# FMC_ADC_128CH_10B.net
KiCad netlist of a schematic drawn in Altium Designer
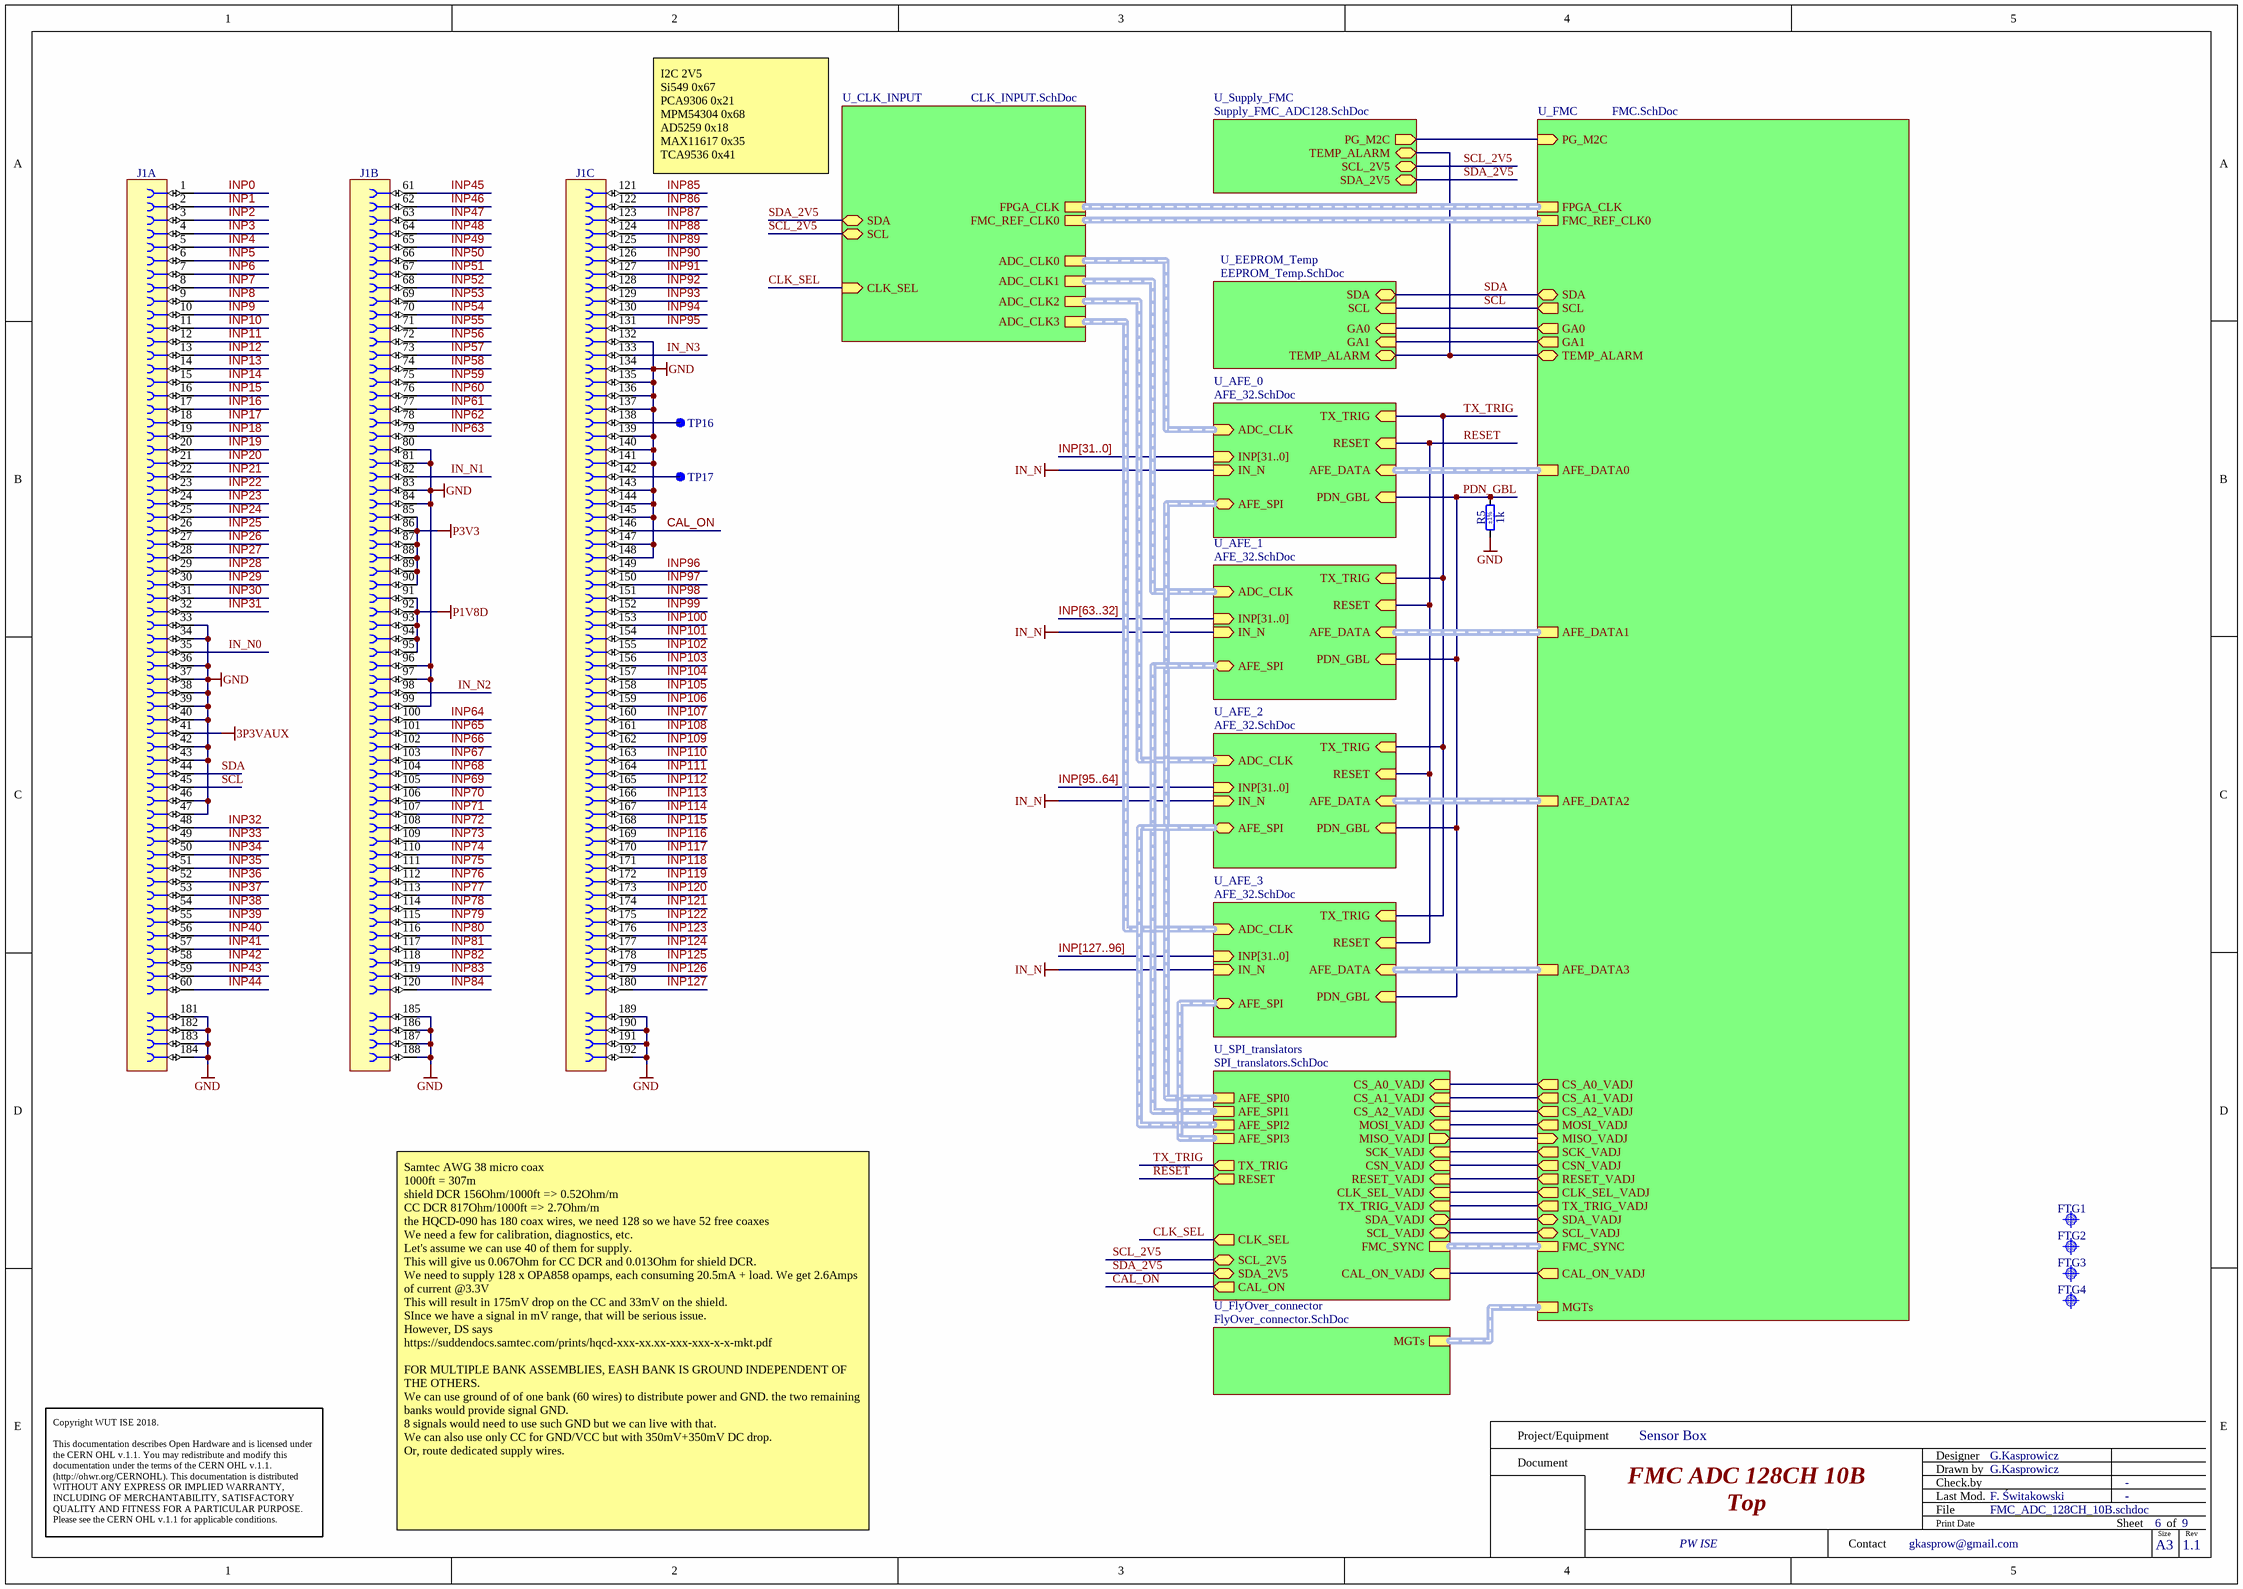
[diagram p0: FMC_ADC_128CH_10B.schdoc]

(export (version "E")
  (design (tool "Eeschema 10.0.6"))
  (components
    (comp (ref "FTG1")
      (value "Use only in PCB")
      (footprint "FIDUCIAL_TOP_C100-200")
      (description "Fiducial Target")
      (fields (field (name "PART NUMBER") "FIDUCIAL_TARGET_C100-200") (field (name "AUTHOR") "CERN DEM JLC"))
      (libsource (lib "Eletro-mechanical") (part "Fiducial Target"))
    )
    (comp (ref "FTG2")
      (value "Use only in PCB")
      (footprint "FIDUCIAL_TOP_S100-200")
      (description "Fiducial Target")
      (fields (field (name "PART NUMBER") "FIDUCIAL_TARGET_S100-200") (field (name "AUTHOR") "CERN DEM JLC"))
      (libsource (lib "Eletro-mechanical") (part "Fiducial Target"))
    )
    (comp (ref "FTG3")
      (value "Use only in PCB")
      (footprint "FIDUCIAL_TOP_C100-200")
      (description "Fiducial Target")
      (fields (field (name "PART NUMBER") "FIDUCIAL_TARGET_C100-200") (field (name "AUTHOR") "CERN DEM JLC"))
      (libsource (lib "Eletro-mechanical") (part "Fiducial Target"))
    )
    (comp (ref "FTG4")
      (value "Use only in PCB")
      (footprint "FIDUCIAL_TOP_S100-200")
      (description "Fiducial Target")
      (fields (field (name "PART NUMBER") "FIDUCIAL_TARGET_S100-200") (field (name "AUTHOR") "CERN DEM JLC"))
      (libsource (lib "Eletro-mechanical") (part "Fiducial Target"))
    )
    (comp (ref "J1")
      (value "~")
      (footprint "SAMTEC_QSH-090-01-L-D-A")
      (description "Connector 180 Female (3x60) + 3x4 GND")
      (fields
        (field (name "PART NUMBER") "SAMTEC_QSH-090-01-L-D-A")
        (field (name "MANUFACTURER") "SAMTEC")
        (field (name "AUTHOR") "CERN DEM MR")
      )
      (libsource (lib "Connectors") (part "Connector 180 Female (3x60) + 3x4 GND"))
    )
    (comp (ref "R5")
      (value "1k")
      (footprint "RESC1005X40N")
      (description "Resistor - 1%")
      (fields
        (field (name "TOLERANCE") "±1%")
        (field (name "PART NUMBER") "R0402_1K_1%_0.0625W_100PPM")
        (field (name "POWER") "0.0625W")
        (field (name "AUTHOR") "CERN DEM JLC")
      )
      (libsource (lib "Resistors") (part "Resistor - 1%"))
    )
    (comp (ref "TP16")
      (value "SMD Pad")
      (footprint "C100")
      (description "Pad")
      (fields (field (name "PART NUMBER") "SMD_PAD_D1MM") (field (name "AUTHOR") "CERN DEM JLC"))
      (libsource (lib "Eletro-mechanical") (part "Single SMD Pad (Round)"))
    )
    (comp (ref "TP17")
      (value "SMD Pad")
      (footprint "C100")
      (description "Pad")
      (fields (field (name "PART NUMBER") "SMD_PAD_D1MM") (field (name "AUTHOR") "CERN DEM JLC"))
      (libsource (lib "Eletro-mechanical") (part "Single SMD Pad (Round)"))
    )
  )
  (nets
    (net (code "13") (name "/CAL_ON") (class "Default")
      (node (ref "J1") (pin "146") (pinfunction "146_146") (pintype "bidirectional"))
    )
    (net (code "26") (name "/INP0") (class "Default")
      (node (ref "J1") (pin "1") (pinfunction "1_1") (pintype "bidirectional"))
    )
    (net (code "27") (name "/INP1") (class "Default")
      (node (ref "J1") (pin "2") (pinfunction "2_2") (pintype "bidirectional"))
    )
    (net (code "28") (name "/INP2") (class "Default")
      (node (ref "J1") (pin "3") (pinfunction "3_3") (pintype "bidirectional"))
    )
    (net (code "29") (name "/INP3") (class "Default")
      (node (ref "J1") (pin "4") (pinfunction "4_4") (pintype "bidirectional"))
    )
    (net (code "30") (name "/INP4") (class "Default")
      (node (ref "J1") (pin "5") (pinfunction "5_5") (pintype "bidirectional"))
    )
    (net (code "31") (name "/INP5") (class "Default")
      (node (ref "J1") (pin "6") (pinfunction "6_6") (pintype "bidirectional"))
    )
    (net (code "32") (name "/INP6") (class "Default")
      (node (ref "J1") (pin "7") (pinfunction "7_7") (pintype "bidirectional"))
    )
    (net (code "33") (name "/INP7") (class "Default")
      (node (ref "J1") (pin "8") (pinfunction "8_8") (pintype "bidirectional"))
    )
    (net (code "34") (name "/INP8") (class "Default")
      (node (ref "J1") (pin "9") (pinfunction "9_9") (pintype "bidirectional"))
    )
    (net (code "35") (name "/INP9") (class "Default")
      (node (ref "J1") (pin "10") (pinfunction "10_10") (pintype "bidirectional"))
    )
    (net (code "36") (name "/INP10") (class "Default")
      (node (ref "J1") (pin "11") (pinfunction "11_11") (pintype "bidirectional"))
    )
    (net (code "37") (name "/INP11") (class "Default")
      (node (ref "J1") (pin "12") (pinfunction "12_12") (pintype "bidirectional"))
    )
    (net (code "38") (name "/INP12") (class "Default")
      (node (ref "J1") (pin "13") (pinfunction "13_13") (pintype "bidirectional"))
    )
    (net (code "39") (name "/INP13") (class "Default")
      (node (ref "J1") (pin "14") (pinfunction "14_14") (pintype "bidirectional"))
    )
    (net (code "40") (name "/INP14") (class "Default")
      (node (ref "J1") (pin "15") (pinfunction "15_15") (pintype "bidirectional"))
    )
    (net (code "41") (name "/INP15") (class "Default")
      (node (ref "J1") (pin "16") (pinfunction "16_16") (pintype "bidirectional"))
    )
    (net (code "42") (name "/INP16") (class "Default")
      (node (ref "J1") (pin "17") (pinfunction "17_17") (pintype "bidirectional"))
    )
    (net (code "43") (name "/INP17") (class "Default")
      (node (ref "J1") (pin "18") (pinfunction "18_18") (pintype "bidirectional"))
    )
    (net (code "44") (name "/INP18") (class "Default")
      (node (ref "J1") (pin "19") (pinfunction "19_19") (pintype "bidirectional"))
    )
    (net (code "45") (name "/INP19") (class "Default")
      (node (ref "J1") (pin "20") (pinfunction "20_20") (pintype "bidirectional"))
    )
    (net (code "46") (name "/INP20") (class "Default")
      (node (ref "J1") (pin "21") (pinfunction "21_21") (pintype "bidirectional"))
    )
    (net (code "47") (name "/INP21") (class "Default")
      (node (ref "J1") (pin "22") (pinfunction "22_22") (pintype "bidirectional"))
    )
    (net (code "48") (name "/INP22") (class "Default")
      (node (ref "J1") (pin "23") (pinfunction "23_23") (pintype "bidirectional"))
    )
    (net (code "49") (name "/INP23") (class "Default")
      (node (ref "J1") (pin "24") (pinfunction "24_24") (pintype "bidirectional"))
    )
    (net (code "50") (name "/INP24") (class "Default")
      (node (ref "J1") (pin "25") (pinfunction "25_25") (pintype "bidirectional"))
    )
    (net (code "51") (name "/INP25") (class "Default")
      (node (ref "J1") (pin "26") (pinfunction "26_26") (pintype "bidirectional"))
    )
    (net (code "52") (name "/INP26") (class "Default")
      (node (ref "J1") (pin "27") (pinfunction "27_27") (pintype "bidirectional"))
    )
    (net (code "53") (name "/INP27") (class "Default")
      (node (ref "J1") (pin "28") (pinfunction "28_28") (pintype "bidirectional"))
    )
    (net (code "54") (name "/INP28") (class "Default")
      (node (ref "J1") (pin "29") (pinfunction "29_29") (pintype "bidirectional"))
    )
    (net (code "55") (name "/INP29") (class "Default")
      (node (ref "J1") (pin "30") (pinfunction "30_30") (pintype "bidirectional"))
    )
    (net (code "56") (name "/INP30") (class "Default")
      (node (ref "J1") (pin "31") (pinfunction "31_31") (pintype "bidirectional"))
    )
    (net (code "57") (name "/INP31") (class "Default")
      (node (ref "J1") (pin "32") (pinfunction "32_32") (pintype "bidirectional"))
    )
    (net (code "58") (name "/INP32") (class "Default")
      (node (ref "J1") (pin "48") (pinfunction "48_48") (pintype "bidirectional"))
    )
    (net (code "59") (name "/INP33") (class "Default")
      (node (ref "J1") (pin "49") (pinfunction "49_49") (pintype "bidirectional"))
    )
    (net (code "60") (name "/INP34") (class "Default")
      (node (ref "J1") (pin "50") (pinfunction "50_50") (pintype "bidirectional"))
    )
    (net (code "61") (name "/INP35") (class "Default")
      (node (ref "J1") (pin "51") (pinfunction "51_51") (pintype "bidirectional"))
    )
    (net (code "62") (name "/INP36") (class "Default")
      (node (ref "J1") (pin "52") (pinfunction "52_52") (pintype "bidirectional"))
    )
    (net (code "63") (name "/INP37") (class "Default")
      (node (ref "J1") (pin "53") (pinfunction "53_53") (pintype "bidirectional"))
    )
    (net (code "64") (name "/INP38") (class "Default")
      (node (ref "J1") (pin "54") (pinfunction "54_54") (pintype "bidirectional"))
    )
    (net (code "65") (name "/INP39") (class "Default")
      (node (ref "J1") (pin "55") (pinfunction "55_55") (pintype "bidirectional"))
    )
    (net (code "66") (name "/INP40") (class "Default")
      (node (ref "J1") (pin "56") (pinfunction "56_56") (pintype "bidirectional"))
    )
    (net (code "67") (name "/INP41") (class "Default")
      (node (ref "J1") (pin "57") (pinfunction "57_57") (pintype "bidirectional"))
    )
    (net (code "68") (name "/INP42") (class "Default")
      (node (ref "J1") (pin "58") (pinfunction "58_58") (pintype "bidirectional"))
    )
    (net (code "69") (name "/INP43") (class "Default")
      (node (ref "J1") (pin "59") (pinfunction "59_59") (pintype "bidirectional"))
    )
    (net (code "70") (name "/INP44") (class "Default")
      (node (ref "J1") (pin "60") (pinfunction "60_60") (pintype "bidirectional"))
    )
    (net (code "71") (name "/INP45") (class "Default")
      (node (ref "J1") (pin "61") (pinfunction "61_61") (pintype "bidirectional"))
    )
    (net (code "72") (name "/INP46") (class "Default")
      (node (ref "J1") (pin "62") (pinfunction "62_62") (pintype "bidirectional"))
    )
    (net (code "73") (name "/INP47") (class "Default")
      (node (ref "J1") (pin "63") (pinfunction "63_63") (pintype "bidirectional"))
    )
    (net (code "74") (name "/INP48") (class "Default")
      (node (ref "J1") (pin "64") (pinfunction "64_64") (pintype "bidirectional"))
    )
    (net (code "75") (name "/INP49") (class "Default")
      (node (ref "J1") (pin "65") (pinfunction "65_65") (pintype "bidirectional"))
    )
    (net (code "76") (name "/INP50") (class "Default")
      (node (ref "J1") (pin "66") (pinfunction "66_66") (pintype "bidirectional"))
    )
    (net (code "77") (name "/INP51") (class "Default")
      (node (ref "J1") (pin "67") (pinfunction "67_67") (pintype "bidirectional"))
    )
    (net (code "78") (name "/INP52") (class "Default")
      (node (ref "J1") (pin "68") (pinfunction "68_68") (pintype "bidirectional"))
    )
    (net (code "79") (name "/INP53") (class "Default")
      (node (ref "J1") (pin "69") (pinfunction "69_69") (pintype "bidirectional"))
    )
    (net (code "80") (name "/INP54") (class "Default")
      (node (ref "J1") (pin "70") (pinfunction "70_70") (pintype "bidirectional"))
    )
    (net (code "81") (name "/INP55") (class "Default")
      (node (ref "J1") (pin "71") (pinfunction "71_71") (pintype "bidirectional"))
    )
    (net (code "82") (name "/INP56") (class "Default")
      (node (ref "J1") (pin "72") (pinfunction "72_72") (pintype "bidirectional"))
    )
    (net (code "83") (name "/INP57") (class "Default")
      (node (ref "J1") (pin "73") (pinfunction "73_73") (pintype "bidirectional"))
    )
    (net (code "84") (name "/INP58") (class "Default")
      (node (ref "J1") (pin "74") (pinfunction "74_74") (pintype "bidirectional"))
    )
    (net (code "85") (name "/INP59") (class "Default")
      (node (ref "J1") (pin "75") (pinfunction "75_75") (pintype "bidirectional"))
    )
    (net (code "86") (name "/INP60") (class "Default")
      (node (ref "J1") (pin "76") (pinfunction "76_76") (pintype "bidirectional"))
    )
    (net (code "87") (name "/INP61") (class "Default")
      (node (ref "J1") (pin "77") (pinfunction "77_77") (pintype "bidirectional"))
    )
    (net (code "88") (name "/INP62") (class "Default")
      (node (ref "J1") (pin "78") (pinfunction "78_78") (pintype "bidirectional"))
    )
    (net (code "89") (name "/INP63") (class "Default")
      (node (ref "J1") (pin "79") (pinfunction "79_79") (pintype "bidirectional"))
    )
    (net (code "90") (name "/INP64") (class "Default")
      (node (ref "J1") (pin "100") (pinfunction "100_100") (pintype "bidirectional"))
    )
    (net (code "91") (name "/INP65") (class "Default")
      (node (ref "J1") (pin "101") (pinfunction "101_101") (pintype "bidirectional"))
    )
    (net (code "92") (name "/INP66") (class "Default")
      (node (ref "J1") (pin "102") (pinfunction "102_102") (pintype "bidirectional"))
    )
    (net (code "93") (name "/INP67") (class "Default")
      (node (ref "J1") (pin "103") (pinfunction "103_103") (pintype "bidirectional"))
    )
    (net (code "94") (name "/INP68") (class "Default")
      (node (ref "J1") (pin "104") (pinfunction "104_104") (pintype "bidirectional"))
    )
    (net (code "95") (name "/INP69") (class "Default")
      (node (ref "J1") (pin "105") (pinfunction "105_105") (pintype "bidirectional"))
    )
    (net (code "96") (name "/INP70") (class "Default")
      (node (ref "J1") (pin "106") (pinfunction "106_106") (pintype "bidirectional"))
    )
    (net (code "97") (name "/INP71") (class "Default")
      (node (ref "J1") (pin "107") (pinfunction "107_107") (pintype "bidirectional"))
    )
    (net (code "98") (name "/INP72") (class "Default")
      (node (ref "J1") (pin "108") (pinfunction "108_108") (pintype "bidirectional"))
    )
    (net (code "99") (name "/INP73") (class "Default")
      (node (ref "J1") (pin "109") (pinfunction "109_109") (pintype "bidirectional"))
    )
    (net (code "100") (name "/INP74") (class "Default")
      (node (ref "J1") (pin "110") (pinfunction "110_110") (pintype "bidirectional"))
    )
    (net (code "101") (name "/INP75") (class "Default")
      (node (ref "J1") (pin "111") (pinfunction "111_111") (pintype "bidirectional"))
    )
    (net (code "102") (name "/INP76") (class "Default")
      (node (ref "J1") (pin "112") (pinfunction "112_112") (pintype "bidirectional"))
    )
    (net (code "103") (name "/INP77") (class "Default")
      (node (ref "J1") (pin "113") (pinfunction "113_113") (pintype "bidirectional"))
    )
    (net (code "104") (name "/INP78") (class "Default")
      (node (ref "J1") (pin "114") (pinfunction "114_114") (pintype "bidirectional"))
    )
    (net (code "105") (name "/INP79") (class "Default")
      (node (ref "J1") (pin "115") (pinfunction "115_115") (pintype "bidirectional"))
    )
    (net (code "106") (name "/INP80") (class "Default")
      (node (ref "J1") (pin "116") (pinfunction "116_116") (pintype "bidirectional"))
    )
    (net (code "107") (name "/INP81") (class "Default")
      (node (ref "J1") (pin "117") (pinfunction "117_117") (pintype "bidirectional"))
    )
    (net (code "108") (name "/INP82") (class "Default")
      (node (ref "J1") (pin "118") (pinfunction "118_118") (pintype "bidirectional"))
    )
    (net (code "109") (name "/INP83") (class "Default")
      (node (ref "J1") (pin "119") (pinfunction "119_119") (pintype "bidirectional"))
    )
    (net (code "110") (name "/INP84") (class "Default")
      (node (ref "J1") (pin "120") (pinfunction "120_120") (pintype "bidirectional"))
    )
    (net (code "111") (name "/INP85") (class "Default")
      (node (ref "J1") (pin "121") (pinfunction "121_121") (pintype "bidirectional"))
    )
    (net (code "112") (name "/INP86") (class "Default")
      (node (ref "J1") (pin "122") (pinfunction "122_122") (pintype "bidirectional"))
    )
    (net (code "113") (name "/INP87") (class "Default")
      (node (ref "J1") (pin "123") (pinfunction "123_123") (pintype "bidirectional"))
    )
    (net (code "114") (name "/INP88") (class "Default")
      (node (ref "J1") (pin "124") (pinfunction "124_124") (pintype "bidirectional"))
    )
    (net (code "115") (name "/INP89") (class "Default")
      (node (ref "J1") (pin "125") (pinfunction "125_125") (pintype "bidirectional"))
    )
    (net (code "116") (name "/INP90") (class "Default")
      (node (ref "J1") (pin "126") (pinfunction "126_126") (pintype "bidirectional"))
    )
    (net (code "117") (name "/INP91") (class "Default")
      (node (ref "J1") (pin "127") (pinfunction "127_127") (pintype "bidirectional"))
    )
    (net (code "118") (name "/INP92") (class "Default")
      (node (ref "J1") (pin "128") (pinfunction "128_128") (pintype "bidirectional"))
    )
    (net (code "119") (name "/INP93") (class "Default")
      (node (ref "J1") (pin "129") (pinfunction "129_129") (pintype "bidirectional"))
    )
    (net (code "120") (name "/INP94") (class "Default")
      (node (ref "J1") (pin "130") (pinfunction "130_130") (pintype "bidirectional"))
    )
    (net (code "121") (name "/INP95") (class "Default")
      (node (ref "J1") (pin "131") (pinfunction "131_131") (pintype "bidirectional"))
    )
    (net (code "122") (name "/INP96") (class "Default")
      (node (ref "J1") (pin "149") (pinfunction "149_149") (pintype "bidirectional"))
    )
    (net (code "123") (name "/INP97") (class "Default")
      (node (ref "J1") (pin "150") (pinfunction "150_150") (pintype "bidirectional"))
    )
    (net (code "124") (name "/INP98") (class "Default")
      (node (ref "J1") (pin "151") (pinfunction "151_151") (pintype "bidirectional"))
    )
    (net (code "125") (name "/INP99") (class "Default")
      (node (ref "J1") (pin "152") (pinfunction "152_152") (pintype "bidirectional"))
    )
    (net (code "126") (name "/INP100") (class "Default")
      (node (ref "J1") (pin "153") (pinfunction "153_153") (pintype "bidirectional"))
    )
    (net (code "127") (name "/INP101") (class "Default")
      (node (ref "J1") (pin "154") (pinfunction "154_154") (pintype "bidirectional"))
    )
    (net (code "128") (name "/INP102") (class "Default")
      (node (ref "J1") (pin "155") (pinfunction "155_155") (pintype "bidirectional"))
    )
    (net (code "129") (name "/INP103") (class "Default")
      (node (ref "J1") (pin "156") (pinfunction "156_156") (pintype "bidirectional"))
    )
    (net (code "130") (name "/INP104") (class "Default")
      (node (ref "J1") (pin "157") (pinfunction "157_157") (pintype "bidirectional"))
    )
    (net (code "131") (name "/INP105") (class "Default")
      (node (ref "J1") (pin "158") (pinfunction "158_158") (pintype "bidirectional"))
    )
    (net (code "132") (name "/INP106") (class "Default")
      (node (ref "J1") (pin "159") (pinfunction "159_159") (pintype "bidirectional"))
    )
    (net (code "133") (name "/INP107") (class "Default")
      (node (ref "J1") (pin "160") (pinfunction "160_160") (pintype "bidirectional"))
    )
    (net (code "134") (name "/INP108") (class "Default")
      (node (ref "J1") (pin "161") (pinfunction "161_161") (pintype "bidirectional"))
    )
    (net (code "135") (name "/INP109") (class "Default")
      (node (ref "J1") (pin "162") (pinfunction "162_162") (pintype "bidirectional"))
    )
    (net (code "136") (name "/INP110") (class "Default")
      (node (ref "J1") (pin "163") (pinfunction "163_163") (pintype "bidirectional"))
    )
    (net (code "137") (name "/INP111") (class "Default")
      (node (ref "J1") (pin "164") (pinfunction "164_164") (pintype "bidirectional"))
    )
    (net (code "138") (name "/INP112") (class "Default")
      (node (ref "J1") (pin "165") (pinfunction "165_165") (pintype "bidirectional"))
    )
    (net (code "139") (name "/INP113") (class "Default")
      (node (ref "J1") (pin "166") (pinfunction "166_166") (pintype "bidirectional"))
    )
    (net (code "140") (name "/INP114") (class "Default")
      (node (ref "J1") (pin "167") (pinfunction "167_167") (pintype "bidirectional"))
    )
    (net (code "141") (name "/INP115") (class "Default")
      (node (ref "J1") (pin "168") (pinfunction "168_168") (pintype "bidirectional"))
    )
    (net (code "142") (name "/INP116") (class "Default")
      (node (ref "J1") (pin "169") (pinfunction "169_169") (pintype "bidirectional"))
    )
    (net (code "143") (name "/INP117") (class "Default")
      (node (ref "J1") (pin "170") (pinfunction "170_170") (pintype "bidirectional"))
    )
    (net (code "144") (name "/INP118") (class "Default")
      (node (ref "J1") (pin "171") (pinfunction "171_171") (pintype "bidirectional"))
    )
    (net (code "145") (name "/INP119") (class "Default")
      (node (ref "J1") (pin "172") (pinfunction "172_172") (pintype "bidirectional"))
    )
    (net (code "146") (name "/INP120") (class "Default")
      (node (ref "J1") (pin "173") (pinfunction "173_173") (pintype "bidirectional"))
    )
    (net (code "147") (name "/INP121") (class "Default")
      (node (ref "J1") (pin "174") (pinfunction "174_174") (pintype "bidirectional"))
    )
    (net (code "148") (name "/INP122") (class "Default")
      (node (ref "J1") (pin "175") (pinfunction "175_175") (pintype "bidirectional"))
    )
    (net (code "149") (name "/INP123") (class "Default")
      (node (ref "J1") (pin "176") (pinfunction "176_176") (pintype "bidirectional"))
    )
    (net (code "150") (name "/INP124") (class "Default")
      (node (ref "J1") (pin "177") (pinfunction "177_177") (pintype "bidirectional"))
    )
    (net (code "151") (name "/INP125") (class "Default")
      (node (ref "J1") (pin "178") (pinfunction "178_178") (pintype "bidirectional"))
    )
    (net (code "152") (name "/INP126") (class "Default")
      (node (ref "J1") (pin "179") (pinfunction "179_179") (pintype "bidirectional"))
    )
    (net (code "153") (name "/INP127") (class "Default")
      (node (ref "J1") (pin "180") (pinfunction "180_180") (pintype "bidirectional"))
    )
    (net (code "158") (name "/IN_N0") (class "Default")
      (node (ref "J1") (pin "35") (pinfunction "35_35") (pintype "bidirectional"))
    )
    (net (code "159") (name "/IN_N1") (class "Default")
      (node (ref "J1") (pin "82") (pinfunction "82_82") (pintype "bidirectional"))
    )
    (net (code "160") (name "/IN_N2") (class "Default")
      (node (ref "J1") (pin "98") (pinfunction "98_98") (pintype "bidirectional"))
    )
    (net (code "161") (name "/IN_N3") (class "Default")
      (node (ref "J1") (pin "133") (pinfunction "133_133") (pintype "bidirectional"))
    )
    (net (code "165") (name "/PDN_GBL") (class "Default")
      (node (ref "R5") (pin "2") (pinfunction "2_2") (pintype "passive"))
    )
    (net (code "170") (name "/SCL") (class "Default")
      (node (ref "J1") (pin "45") (pinfunction "45_45") (pintype "bidirectional"))
    )
    (net (code "173") (name "/SDA") (class "Default")
      (node (ref "J1") (pin "44") (pinfunction "44_44") (pintype "bidirectional"))
    )
    (net (code "179") (name "3P3VAUX") (class "Default")
      (node (ref "J1") (pin "41") (pinfunction "41_41") (pintype "bidirectional"))
    )
    (net (code "180") (name "GND") (class "Default")
      (node (ref "J1") (pin "132") (pinfunction "132_132") (pintype "bidirectional"))
      (node (ref "J1") (pin "134") (pinfunction "134_134") (pintype "bidirectional"))
      (node (ref "J1") (pin "135") (pinfunction "135_135") (pintype "bidirectional"))
      (node (ref "J1") (pin "136") (pinfunction "136_136") (pintype "bidirectional"))
      (node (ref "J1") (pin "137") (pinfunction "137_137") (pintype "bidirectional"))
      (node (ref "J1") (pin "139") (pinfunction "139_139") (pintype "bidirectional"))
      (node (ref "J1") (pin "140") (pinfunction "140_140") (pintype "bidirectional"))
      (node (ref "J1") (pin "141") (pinfunction "141_141") (pintype "bidirectional"))
      (node (ref "J1") (pin "143") (pinfunction "143_143") (pintype "bidirectional"))
      (node (ref "J1") (pin "144") (pinfunction "144_144") (pintype "bidirectional"))
      (node (ref "J1") (pin "145") (pinfunction "145_145") (pintype "bidirectional"))
      (node (ref "J1") (pin "147") (pinfunction "147_147") (pintype "bidirectional"))
      (node (ref "J1") (pin "148") (pinfunction "148_148") (pintype "bidirectional"))
      (node (ref "J1") (pin "181") (pinfunction "181_181") (pintype "bidirectional"))
      (node (ref "J1") (pin "182") (pinfunction "182_182") (pintype "bidirectional"))
      (node (ref "J1") (pin "183") (pinfunction "183_183") (pintype "bidirectional"))
      (node (ref "J1") (pin "184") (pinfunction "184_184") (pintype "bidirectional"))
      (node (ref "J1") (pin "185") (pinfunction "185_185") (pintype "bidirectional"))
      (node (ref "J1") (pin "186") (pinfunction "186_186") (pintype "bidirectional"))
      (node (ref "J1") (pin "187") (pinfunction "187_187") (pintype "bidirectional"))
      (node (ref "J1") (pin "188") (pinfunction "188_188") (pintype "bidirectional"))
      (node (ref "J1") (pin "189") (pinfunction "189_189") (pintype "bidirectional"))
      (node (ref "J1") (pin "190") (pinfunction "190_190") (pintype "bidirectional"))
      (node (ref "J1") (pin "191") (pinfunction "191_191") (pintype "bidirectional"))
      (node (ref "J1") (pin "192") (pinfunction "192_192") (pintype "bidirectional"))
      (node (ref "J1") (pin "33") (pinfunction "33_33") (pintype "bidirectional"))
      (node (ref "J1") (pin "34") (pinfunction "34_34") (pintype "bidirectional"))
      (node (ref "J1") (pin "36") (pinfunction "36_36") (pintype "bidirectional"))
      (node (ref "J1") (pin "37") (pinfunction "37_37") (pintype "bidirectional"))
      (node (ref "J1") (pin "38") (pinfunction "38_38") (pintype "bidirectional"))
      (node (ref "J1") (pin "39") (pinfunction "39_39") (pintype "bidirectional"))
      (node (ref "J1") (pin "40") (pinfunction "40_40") (pintype "bidirectional"))
      (node (ref "J1") (pin "42") (pinfunction "42_42") (pintype "bidirectional"))
      (node (ref "J1") (pin "43") (pinfunction "43_43") (pintype "bidirectional"))
      (node (ref "J1") (pin "46") (pinfunction "46_46") (pintype "bidirectional"))
      (node (ref "J1") (pin "47") (pinfunction "47_47") (pintype "bidirectional"))
      (node (ref "J1") (pin "80") (pinfunction "80_80") (pintype "bidirectional"))
      (node (ref "J1") (pin "81") (pinfunction "81_81") (pintype "bidirectional"))
      (node (ref "J1") (pin "83") (pinfunction "83_83") (pintype "bidirectional"))
      (node (ref "J1") (pin "84") (pinfunction "84_84") (pintype "bidirectional"))
      (node (ref "J1") (pin "96") (pinfunction "96_96") (pintype "bidirectional"))
      (node (ref "J1") (pin "97") (pinfunction "97_97") (pintype "bidirectional"))
      (node (ref "J1") (pin "99") (pinfunction "99_99") (pintype "bidirectional"))
      (node (ref "R5") (pin "1") (pinfunction "1_1") (pintype "passive"))
    )
    (net (code "182") (name "Net-(J1-Pad138)") (class "Default")
      (node (ref "J1") (pin "138") (pinfunction "138_138") (pintype "bidirectional"))
      (node (ref "TP16") (pin "1") (pinfunction "1_1") (pintype "bidirectional"))
    )
    (net (code "183") (name "Net-(J1-Pad142)") (class "Default")
      (node (ref "J1") (pin "142") (pinfunction "142_142") (pintype "bidirectional"))
      (node (ref "TP17") (pin "1") (pinfunction "1_1") (pintype "bidirectional"))
    )
    (net (code "184") (name "P1V8D") (class "Default")
      (node (ref "J1") (pin "91") (pinfunction "91_91") (pintype "bidirectional"))
      (node (ref "J1") (pin "92") (pinfunction "92_92") (pintype "bidirectional"))
      (node (ref "J1") (pin "93") (pinfunction "93_93") (pintype "bidirectional"))
      (node (ref "J1") (pin "94") (pinfunction "94_94") (pintype "bidirectional"))
      (node (ref "J1") (pin "95") (pinfunction "95_95") (pintype "bidirectional"))
    )
    (net (code "185") (name "P3V3") (class "Default")
      (node (ref "J1") (pin "85") (pinfunction "85_85") (pintype "bidirectional"))
      (node (ref "J1") (pin "86") (pinfunction "86_86") (pintype "bidirectional"))
      (node (ref "J1") (pin "87") (pinfunction "87_87") (pintype "bidirectional"))
      (node (ref "J1") (pin "88") (pinfunction "88_88") (pintype "bidirectional"))
      (node (ref "J1") (pin "89") (pinfunction "89_89") (pintype "bidirectional"))
      (node (ref "J1") (pin "90") (pinfunction "90_90") (pintype "bidirectional"))
    )
  )
)
